# SP.net
KiCad netlist of a schematic drawn in EAGLE
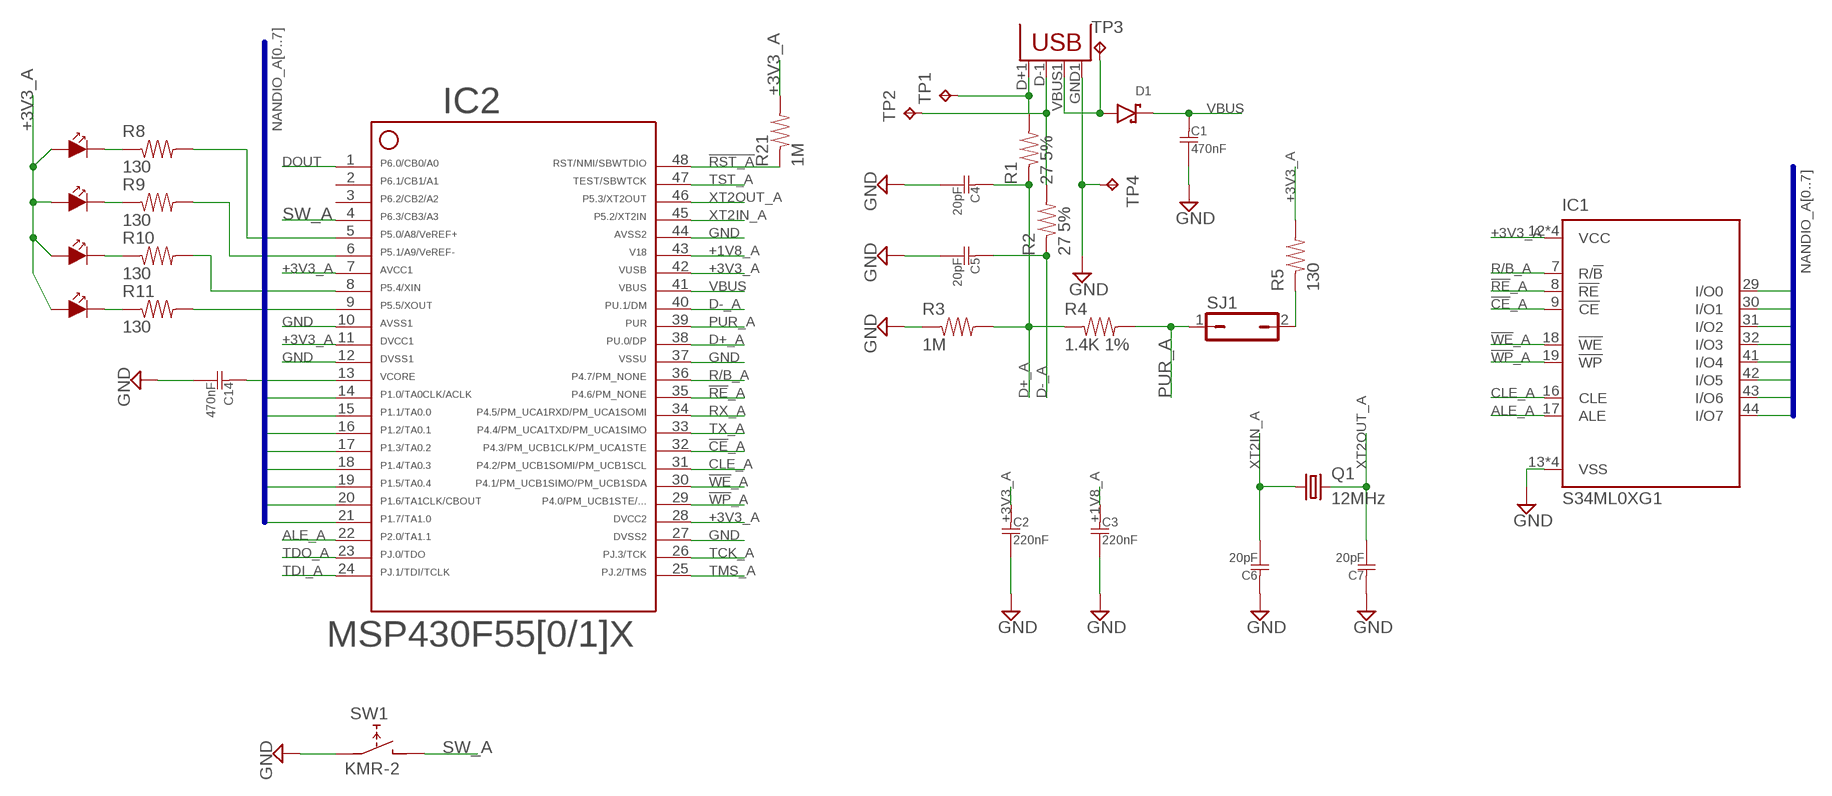
[diagram p0: schematic, sheet 1]
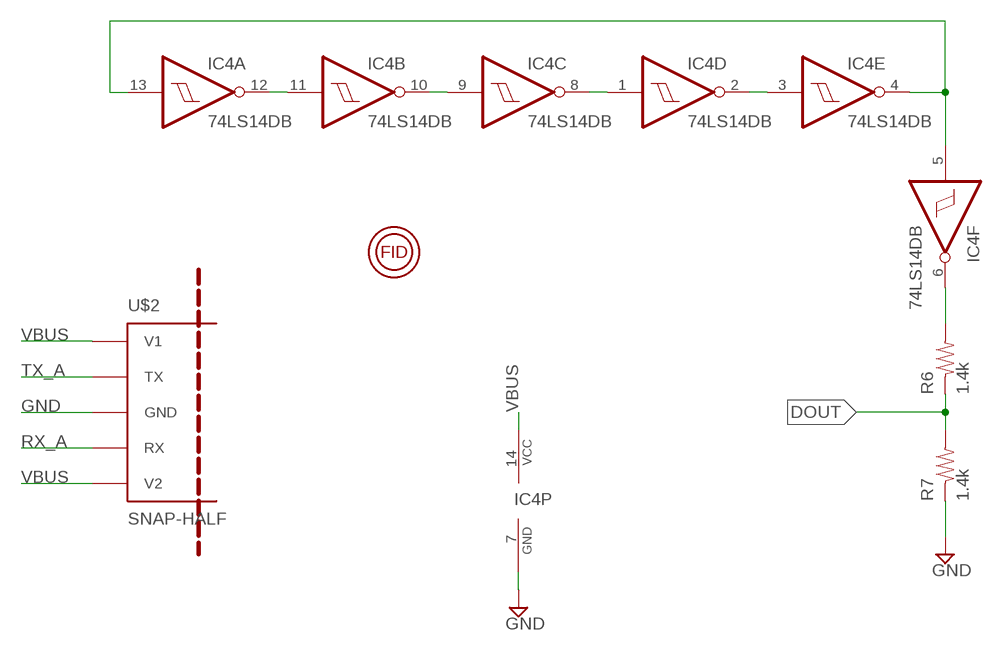
[diagram p1: schematic, sheet 2]

(export (version "E")
  (design (tool "Eeschema 10.0.6"))
  (components
    (comp (ref "IC4")
      (value "74LS14DB")
      (footprint "eagle-import:SSOP14")
      (libsource (lib "eagle-import") (part "7414DBLS"))
    )
    (comp (ref "R6")
      (value "1.4k")
      (footprint "eagle-import:R0805")
      (libsource (lib "eagle-import") (part "R0805"))
    )
    (comp (ref "R7")
      (value "1.4k")
      (footprint "eagle-import:R0805")
      (libsource (lib "eagle-import") (part "R0805"))
    )
    (comp (ref "U$2")
      (value "SNAP-HALF")
      (footprint "eagle-import:SNAP-HALF")
      (libsource (lib "eagle-import") (part "SNAP-HALF"))
    )
    (comp (ref "U$3")
      (value "FIDUCAL")
      (footprint "eagle-import:FIDUCAL")
      (libsource (lib "eagle-import") (part "FIDUCAL"))
    )
    (comp (ref "C1")
      (value "470nF")
      (footprint "eagle-import:R0805")
      (libsource (lib "eagle-import") (part "C0805"))
    )
    (comp (ref "C2")
      (value "220nF")
      (footprint "eagle-import:R0805")
      (libsource (lib "eagle-import") (part "C0805"))
    )
    (comp (ref "C3")
      (value "220nF")
      (footprint "eagle-import:R0805")
      (libsource (lib "eagle-import") (part "C0805"))
    )
    (comp (ref "C4")
      (value "20pF")
      (footprint "eagle-import:R0805")
      (libsource (lib "eagle-import") (part "C0805"))
    )
    (comp (ref "C5")
      (value "20pF")
      (footprint "eagle-import:R0805")
      (libsource (lib "eagle-import") (part "C0805"))
    )
    (comp (ref "C6")
      (value "20pF")
      (footprint "eagle-import:R0805")
      (libsource (lib "eagle-import") (part "C0805"))
    )
    (comp (ref "C7")
      (value "20pF")
      (footprint "eagle-import:R0805")
      (libsource (lib "eagle-import") (part "C0805"))
    )
    (comp (ref "C14")
      (value "470nF")
      (footprint "eagle-import:R0805")
      (libsource (lib "eagle-import") (part "C0805"))
    )
    (comp (ref "D1")
      (value "D-SCHOTTKY")
      (footprint "eagle-import:SOD123")
      (libsource (lib "eagle-import") (part "D-SCHOTTKY"))
    )
    (comp (ref "IC1")
      (value "S34ML0XG1")
      (footprint "eagle-import:TSOP48")
      (libsource (lib "eagle-import") (part "S34ML0XG1"))
    )
    (comp (ref "IC2")
      (value "F5508")
      (footprint "eagle-import:PT48")
      (libsource (lib "eagle-import") (part "F55[0/1]X---PT48"))
    )
    (comp (ref "JP1")
      (value "USBA-SMD-MALE")
      (footprint "eagle-import:USB-A-SMT-MALE")
      (libsource (lib "eagle-import") (part "USBA-SMD-MALE"))
    )
    (comp (ref "Q1")
      (value "12MHz")
      (footprint "eagle-import:CSM-3X")
      (libsource (lib "eagle-import") (part "CRYSTALCSM-3X"))
    )
    (comp (ref "R1")
      (value "27 5%")
      (footprint "eagle-import:R0805")
      (libsource (lib "eagle-import") (part "R0805"))
    )
    (comp (ref "R2")
      (value "27 5%")
      (footprint "eagle-import:R0805")
      (libsource (lib "eagle-import") (part "R0805"))
    )
    (comp (ref "R3")
      (value "1M")
      (footprint "eagle-import:R0805")
      (libsource (lib "eagle-import") (part "R0805"))
    )
    (comp (ref "R4")
      (value "1.4K 1%")
      (footprint "eagle-import:R0805")
      (libsource (lib "eagle-import") (part "R0805"))
    )
    (comp (ref "R5")
      (value "130")
      (footprint "eagle-import:R0805")
      (libsource (lib "eagle-import") (part "R0805"))
    )
    (comp (ref "R8")
      (value "130")
      (footprint "eagle-import:R0805")
      (libsource (lib "eagle-import") (part "R0805"))
    )
    (comp (ref "R9")
      (value "130")
      (footprint "eagle-import:R0805")
      (libsource (lib "eagle-import") (part "R0805"))
    )
    (comp (ref "R10")
      (value "130")
      (footprint "eagle-import:R0805")
      (libsource (lib "eagle-import") (part "R0805"))
    )
    (comp (ref "R11")
      (value "130")
      (footprint "eagle-import:R0805")
      (libsource (lib "eagle-import") (part "R0805"))
    )
    (comp (ref "R21")
      (value "1M")
      (footprint "eagle-import:R0805")
      (libsource (lib "eagle-import") (part "R0805"))
    )
    (comp (ref "SJ1")
      (value "JP1Q")
      (footprint "eagle-import:JP1")
      (libsource (lib "eagle-import") (part "JP1Q"))
    )
    (comp (ref "SW1")
      (value "KMR-2")
      (footprint "eagle-import:KMR-2-SWITCH")
      (libsource (lib "eagle-import") (part "KMR-2"))
    )
    (comp (ref "TP1")
      (value "TPTP13R")
      (footprint "eagle-import:TP13R")
      (libsource (lib "eagle-import") (part "TPTP13R"))
    )
    (comp (ref "TP2")
      (value "TPTP13R")
      (footprint "eagle-import:TP13R")
      (libsource (lib "eagle-import") (part "TPTP13R"))
    )
    (comp (ref "TP3")
      (value "TPTP13R")
      (footprint "eagle-import:TP13R")
      (libsource (lib "eagle-import") (part "TPTP13R"))
    )
    (comp (ref "TP4")
      (value "TPTP13R")
      (footprint "eagle-import:TP13R")
      (libsource (lib "eagle-import") (part "TPTP13R"))
    )
    (comp (ref "U$5")
      (value "LED")
      (footprint "eagle-import:LED0805")
      (libsource (lib "eagle-import") (part "LED"))
    )
    (comp (ref "U$6")
      (value "LED")
      (footprint "eagle-import:LED0805")
      (libsource (lib "eagle-import") (part "LED"))
    )
    (comp (ref "U$7")
      (value "LED")
      (footprint "eagle-import:LED0805")
      (libsource (lib "eagle-import") (part "LED"))
    )
    (comp (ref "U$8")
      (value "LED")
      (footprint "eagle-import:LED0805")
      (libsource (lib "eagle-import") (part "LED"))
    )
  )
  (nets
    (net (code "1") (name "+1V8_A") (class "Default")
      (node (ref "C3") (pin "P$1") (pinfunction "1_P$1") (pintype "passive"))
      (node (ref "IC2") (pin "43") (pinfunction "43_43") (pintype "power_in"))
    )
    (net (code "2") (name "+3V3_A") (class "Default")
      (node (ref "C2") (pin "P$1") (pinfunction "1_P$1") (pintype "passive"))
      (node (ref "IC1") (pin "12") (pinfunction "VCC_12") (pintype "power_in"))
      (node (ref "IC1") (pin "34") (pinfunction "VCC_34") (pintype "power_in"))
      (node (ref "IC1") (pin "37") (pinfunction "VCC_37") (pintype "power_in"))
      (node (ref "IC1") (pin "39") (pinfunction "VCC_39") (pintype "power_in"))
      (node (ref "IC2") (pin "11") (pinfunction "11_11") (pintype "power_in"))
      (node (ref "IC2") (pin "28") (pinfunction "28_28") (pintype "power_in"))
      (node (ref "IC2") (pin "42") (pinfunction "42_42") (pintype "power_in"))
      (node (ref "IC2") (pin "7") (pinfunction "7_7") (pintype "power_in"))
      (node (ref "R21") (pin "P$2") (pinfunction "2_P$2") (pintype "passive"))
      (node (ref "R5") (pin "P$2") (pinfunction "2_P$2") (pintype "passive"))
      (node (ref "U$5") (pin "ANODE") (pinfunction "ANODE_ANODE") (pintype "passive"))
      (node (ref "U$6") (pin "ANODE") (pinfunction "ANODE_ANODE") (pintype "passive"))
      (node (ref "U$7") (pin "ANODE") (pinfunction "ANODE_ANODE") (pintype "passive"))
      (node (ref "U$8") (pin "ANODE") (pinfunction "ANODE_ANODE") (pintype "passive"))
    )
    (net (code "4") (name "ALE_A") (class "Default")
      (node (ref "IC1") (pin "17") (pinfunction "ALE_17") (pintype "input"))
      (node (ref "IC2") (pin "22") (pinfunction "22_22") (pintype "bidirectional"))
    )
    (net (code "5") (name "CLE_A") (class "Default")
      (node (ref "IC1") (pin "16") (pinfunction "CLE_16") (pintype "input"))
      (node (ref "IC2") (pin "31") (pinfunction "31_31") (pintype "bidirectional"))
    )
    (net (code "6") (name "D+_A") (class "Default")
      (node (ref "C4") (pin "P$1") (pinfunction "1_P$1") (pintype "passive"))
      (node (ref "IC2") (pin "38") (pinfunction "38_38") (pintype "bidirectional"))
      (node (ref "R1") (pin "P$1") (pinfunction "1_P$1") (pintype "passive"))
      (node (ref "R3") (pin "P$2") (pinfunction "2_P$2") (pintype "passive"))
      (node (ref "R4") (pin "P$1") (pinfunction "1_P$1") (pintype "passive"))
    )
    (net (code "7") (name "D-_A") (class "Default")
      (node (ref "C5") (pin "P$1") (pinfunction "1_P$1") (pintype "passive"))
      (node (ref "IC2") (pin "40") (pinfunction "40_40") (pintype "bidirectional"))
      (node (ref "R2") (pin "P$1") (pinfunction "1_P$1") (pintype "passive"))
    )
    (net (code "8") (name "DOUT") (class "Default")
      (node (ref "IC2") (pin "1") (pinfunction "1_1") (pintype "bidirectional"))
      (node (ref "R6") (pin "P$1") (pinfunction "1_P$1") (pintype "passive"))
      (node (ref "R7") (pin "P$2") (pinfunction "2_P$2") (pintype "passive"))
    )
    (net (code "9") (name "GND") (class "Default")
      (node (ref "C1") (pin "P$2") (pinfunction "2_P$2") (pintype "passive"))
      (node (ref "C14") (pin "P$2") (pinfunction "2_P$2") (pintype "passive"))
      (node (ref "C2") (pin "P$2") (pinfunction "2_P$2") (pintype "passive"))
      (node (ref "C3") (pin "P$2") (pinfunction "2_P$2") (pintype "passive"))
      (node (ref "C4") (pin "P$2") (pinfunction "2_P$2") (pintype "passive"))
      (node (ref "C5") (pin "P$2") (pinfunction "2_P$2") (pintype "passive"))
      (node (ref "C6") (pin "P$1") (pinfunction "1_P$1") (pintype "passive"))
      (node (ref "C7") (pin "P$1") (pinfunction "1_P$1") (pintype "passive"))
      (node (ref "IC1") (pin "13") (pinfunction "VSS_13") (pintype "power_in"))
      (node (ref "IC1") (pin "25") (pinfunction "VSS_25") (pintype "power_in"))
      (node (ref "IC1") (pin "36") (pinfunction "VSS_36") (pintype "power_in"))
      (node (ref "IC1") (pin "48") (pinfunction "VSS_48") (pintype "power_in"))
      (node (ref "IC2") (pin "10") (pinfunction "10_10") (pintype "power_in"))
      (node (ref "IC2") (pin "12") (pinfunction "12_12") (pintype "power_in"))
      (node (ref "IC2") (pin "27") (pinfunction "27_27") (pintype "power_in"))
      (node (ref "IC2") (pin "37") (pinfunction "37_37") (pintype "power_in"))
      (node (ref "IC2") (pin "44") (pinfunction "44_44") (pintype "power_in"))
      (node (ref "IC4") (pin "7") (pinfunction "GND_7") (pintype "power_in"))
      (node (ref "JP1") (pin "GND1") (pinfunction "GND_GND1") (pintype "bidirectional"))
      (node (ref "R3") (pin "P$1") (pinfunction "1_P$1") (pintype "passive"))
      (node (ref "R7") (pin "P$1") (pinfunction "1_P$1") (pintype "passive"))
      (node (ref "SW1") (pin "PA1") (pinfunction "A1_PA1") (pintype "passive"))
      (node (ref "SW1") (pin "PA2") (pinfunction "A1_PA2") (pintype "passive"))
      (node (ref "TP4") (pin "TP") (pinfunction "TP_TP") (pintype "input"))
      (node (ref "U$2") (pin "P$3") (pinfunction "GND_P$3") (pintype "bidirectional"))
    )
    (net (code "10") (name "NANDIO_A0") (class "Default")
      (node (ref "IC1") (pin "29") (pinfunction "I/O0_29") (pintype "bidirectional"))
      (node (ref "IC2") (pin "14") (pinfunction "14_14") (pintype "bidirectional"))
    )
    (net (code "11") (name "NANDIO_A1") (class "Default")
      (node (ref "IC1") (pin "30") (pinfunction "I/O1_30") (pintype "bidirectional"))
      (node (ref "IC2") (pin "15") (pinfunction "15_15") (pintype "bidirectional"))
    )
    (net (code "12") (name "NANDIO_A2") (class "Default")
      (node (ref "IC1") (pin "31") (pinfunction "I/O2_31") (pintype "bidirectional"))
      (node (ref "IC2") (pin "16") (pinfunction "16_16") (pintype "bidirectional"))
    )
    (net (code "13") (name "NANDIO_A3") (class "Default")
      (node (ref "IC1") (pin "32") (pinfunction "I/O3_32") (pintype "bidirectional"))
      (node (ref "IC2") (pin "17") (pinfunction "17_17") (pintype "bidirectional"))
    )
    (net (code "14") (name "NANDIO_A4") (class "Default")
      (node (ref "IC1") (pin "41") (pinfunction "I/O4_41") (pintype "bidirectional"))
      (node (ref "IC2") (pin "18") (pinfunction "18_18") (pintype "bidirectional"))
    )
    (net (code "15") (name "NANDIO_A5") (class "Default")
      (node (ref "IC1") (pin "42") (pinfunction "I/O5_42") (pintype "bidirectional"))
      (node (ref "IC2") (pin "19") (pinfunction "19_19") (pintype "bidirectional"))
    )
    (net (code "16") (name "NANDIO_A6") (class "Default")
      (node (ref "IC1") (pin "43") (pinfunction "I/O6_43") (pintype "bidirectional"))
      (node (ref "IC2") (pin "20") (pinfunction "20_20") (pintype "bidirectional"))
    )
    (net (code "17") (name "NANDIO_A7") (class "Default")
      (node (ref "IC1") (pin "44") (pinfunction "I/O7_44") (pintype "bidirectional"))
      (node (ref "IC2") (pin "21") (pinfunction "21_21") (pintype "bidirectional"))
    )
    (net (code "18") (name "Net-(C14-1)") (class "Default")
      (node (ref "C14") (pin "P$1") (pinfunction "1_P$1") (pintype "passive"))
      (node (ref "IC2") (pin "13") (pinfunction "13_13") (pintype "power_in"))
    )
    (net (code "19") (name "Net-(IC4A-I)") (class "Default")
      (node (ref "IC4") (pin "13") (pinfunction "I_13") (pintype "input"))
      (node (ref "IC4") (pin "4") (pinfunction "O_4") (pintype "output"))
      (node (ref "IC4") (pin "5") (pinfunction "I_5") (pintype "input"))
    )
    (net (code "20") (name "Net-(IC4A-O)") (class "Default")
      (node (ref "IC4") (pin "11") (pinfunction "I_11") (pintype "input"))
      (node (ref "IC4") (pin "12") (pinfunction "O_12") (pintype "output"))
    )
    (net (code "21") (name "Net-(IC4B-O)") (class "Default")
      (node (ref "IC4") (pin "10") (pinfunction "O_10") (pintype "output"))
      (node (ref "IC4") (pin "9") (pinfunction "I_9") (pintype "input"))
    )
    (net (code "22") (name "Net-(IC4C-O)") (class "Default")
      (node (ref "IC4") (pin "1") (pinfunction "I_1") (pintype "input"))
      (node (ref "IC4") (pin "8") (pinfunction "O_8") (pintype "output"))
    )
    (net (code "23") (name "Net-(IC4D-O)") (class "Default")
      (node (ref "IC4") (pin "2") (pinfunction "O_2") (pintype "output"))
      (node (ref "IC4") (pin "3") (pinfunction "I_3") (pintype "input"))
    )
    (net (code "24") (name "Net-(IC4F-O)") (class "Default")
      (node (ref "IC4") (pin "6") (pinfunction "O_6") (pintype "output"))
      (node (ref "R6") (pin "P$2") (pinfunction "2_P$2") (pintype "passive"))
    )
    (net (code "25") (name "Net-(JP1-D+)") (class "Default")
      (node (ref "JP1") (pin "D+1") (pinfunction "D+_D+1") (pintype "bidirectional"))
      (node (ref "R1") (pin "P$2") (pinfunction "2_P$2") (pintype "passive"))
      (node (ref "TP1") (pin "TP") (pinfunction "TP_TP") (pintype "input"))
    )
    (net (code "26") (name "Net-(JP1-D-)") (class "Default")
      (node (ref "JP1") (pin "D-1") (pinfunction "D-_D-1") (pintype "bidirectional"))
      (node (ref "R2") (pin "P$2") (pinfunction "2_P$2") (pintype "passive"))
      (node (ref "TP2") (pin "TP") (pinfunction "TP_TP") (pintype "input"))
    )
    (net (code "27") (name "Net-(JP1-VBUS)") (class "Default")
      (node (ref "D1") (pin "ANODE") (pinfunction "ANODE_ANODE") (pintype "passive"))
      (node (ref "JP1") (pin "VBUS1") (pinfunction "VBUS_VBUS1") (pintype "bidirectional"))
      (node (ref "TP3") (pin "TP") (pinfunction "TP_TP") (pintype "input"))
    )
    (net (code "28") (name "Net-(R5-1)") (class "Default")
      (node (ref "R5") (pin "P$1") (pinfunction "1_P$1") (pintype "passive"))
      (node (ref "SJ1") (pin "2") (pinfunction "2_2") (pintype "passive"))
    )
    (net (code "29") (name "Net-(R8-1)") (class "Default")
      (node (ref "R8") (pin "P$1") (pinfunction "1_P$1") (pintype "passive"))
      (node (ref "U$5") (pin "CATHODE") (pinfunction "CATHODE_CATHODE") (pintype "passive"))
    )
    (net (code "30") (name "Net-(R8-2)") (class "Default")
      (node (ref "IC2") (pin "5") (pinfunction "5_5") (pintype "bidirectional"))
      (node (ref "R8") (pin "P$2") (pinfunction "2_P$2") (pintype "passive"))
    )
    (net (code "31") (name "Net-(R9-1)") (class "Default")
      (node (ref "R9") (pin "P$1") (pinfunction "1_P$1") (pintype "passive"))
      (node (ref "U$6") (pin "CATHODE") (pinfunction "CATHODE_CATHODE") (pintype "passive"))
    )
    (net (code "32") (name "Net-(R9-2)") (class "Default")
      (node (ref "IC2") (pin "6") (pinfunction "6_6") (pintype "bidirectional"))
      (node (ref "R9") (pin "P$2") (pinfunction "2_P$2") (pintype "passive"))
    )
    (net (code "33") (name "Net-(R10-1)") (class "Default")
      (node (ref "R10") (pin "P$1") (pinfunction "1_P$1") (pintype "passive"))
      (node (ref "U$7") (pin "CATHODE") (pinfunction "CATHODE_CATHODE") (pintype "passive"))
    )
    (net (code "34") (name "Net-(R10-2)") (class "Default")
      (node (ref "IC2") (pin "8") (pinfunction "8_8") (pintype "bidirectional"))
      (node (ref "R10") (pin "P$2") (pinfunction "2_P$2") (pintype "passive"))
    )
    (net (code "35") (name "Net-(R11-1)") (class "Default")
      (node (ref "R11") (pin "P$1") (pinfunction "1_P$1") (pintype "passive"))
      (node (ref "U$8") (pin "CATHODE") (pinfunction "CATHODE_CATHODE") (pintype "passive"))
    )
    (net (code "36") (name "Net-(R11-2)") (class "Default")
      (node (ref "IC2") (pin "9") (pinfunction "9_9") (pintype "bidirectional"))
      (node (ref "R11") (pin "P$2") (pinfunction "2_P$2") (pintype "passive"))
    )
    (net (code "37") (name "PUR_A") (class "Default")
      (node (ref "IC2") (pin "39") (pinfunction "39_39") (pintype "bidirectional"))
      (node (ref "R4") (pin "P$2") (pinfunction "2_P$2") (pintype "passive"))
      (node (ref "SJ1") (pin "1") (pinfunction "1_1") (pintype "passive"))
    )
    (net (code "38") (name "RX_A") (class "Default")
      (node (ref "IC2") (pin "34") (pinfunction "34_34") (pintype "bidirectional"))
      (node (ref "U$2") (pin "P$4") (pinfunction "RX_P$4") (pintype "bidirectional"))
    )
    (net (code "39") (name "R{slash}B_A") (class "Default")
      (node (ref "IC1") (pin "7") (pinfunction "R/~{B}_7") (pintype "input"))
      (node (ref "IC2") (pin "36") (pinfunction "36_36") (pintype "bidirectional"))
    )
    (net (code "40") (name "SW_A") (class "Default")
      (node (ref "IC2") (pin "4") (pinfunction "4_4") (pintype "bidirectional"))
      (node (ref "SW1") (pin "PB1") (pinfunction "B_PB1") (pintype "passive"))
      (node (ref "SW1") (pin "PB2") (pinfunction "B_PB2") (pintype "passive"))
    )
    (net (code "41") (name "TCK_A") (class "Default")
      (node (ref "IC2") (pin "26") (pinfunction "26_26") (pintype "bidirectional"))
    )
    (net (code "42") (name "TDI_A") (class "Default")
      (node (ref "IC2") (pin "24") (pinfunction "24_24") (pintype "bidirectional"))
    )
    (net (code "43") (name "TDO_A") (class "Default")
      (node (ref "IC2") (pin "23") (pinfunction "23_23") (pintype "bidirectional"))
    )
    (net (code "44") (name "TMS_A") (class "Default")
      (node (ref "IC2") (pin "25") (pinfunction "25_25") (pintype "bidirectional"))
    )
    (net (code "45") (name "TST_A") (class "Default")
      (node (ref "IC2") (pin "47") (pinfunction "47_47") (pintype "input"))
    )
    (net (code "46") (name "TX_A") (class "Default")
      (node (ref "IC2") (pin "33") (pinfunction "33_33") (pintype "bidirectional"))
      (node (ref "U$2") (pin "P$2") (pinfunction "TX_P$2") (pintype "bidirectional"))
    )
    (net (code "47") (name "VBUS") (class "Default")
      (node (ref "C1") (pin "P$1") (pinfunction "1_P$1") (pintype "passive"))
      (node (ref "D1") (pin "CATHODE") (pinfunction "CATHODE_CATHODE") (pintype "passive"))
      (node (ref "IC2") (pin "41") (pinfunction "41_41") (pintype "power_in"))
      (node (ref "IC4") (pin "14") (pinfunction "VCC_14") (pintype "power_in"))
      (node (ref "U$2") (pin "P$1") (pinfunction "V1_P$1") (pintype "bidirectional"))
      (node (ref "U$2") (pin "P$5") (pinfunction "V2_P$5") (pintype "bidirectional"))
    )
    (net (code "48") (name "XT2IN_A") (class "Default")
      (node (ref "C6") (pin "P$2") (pinfunction "2_P$2") (pintype "passive"))
      (node (ref "IC2") (pin "45") (pinfunction "45_45") (pintype "bidirectional"))
      (node (ref "Q1") (pin "P$1") (pinfunction "1_P$1") (pintype "passive"))
    )
    (net (code "49") (name "XT2OUT_A") (class "Default")
      (node (ref "C7") (pin "P$2") (pinfunction "2_P$2") (pintype "passive"))
      (node (ref "IC2") (pin "46") (pinfunction "46_46") (pintype "power_in"))
      (node (ref "Q1") (pin "P$2") (pinfunction "2_P$2") (pintype "passive"))
    )
    (net (code "50") (name "unconnected-(IC2-Pad2)") (class "Default")
      (node (ref "IC2") (pin "2") (pinfunction "2_2") (pintype "bidirectional"))
    )
    (net (code "51") (name "unconnected-(IC2-Pad3)") (class "Default")
      (node (ref "IC2") (pin "3") (pinfunction "3_3") (pintype "bidirectional"))
    )
    (net (code "52") (name "~{CE}_A") (class "Default")
      (node (ref "IC1") (pin "9") (pinfunction "~{CE}_9") (pintype "input"))
      (node (ref "IC2") (pin "32") (pinfunction "32_32") (pintype "bidirectional"))
    )
    (net (code "53") (name "~{RE}_A") (class "Default")
      (node (ref "IC1") (pin "8") (pinfunction "~{RE}_8") (pintype "input"))
      (node (ref "IC2") (pin "35") (pinfunction "35_35") (pintype "bidirectional"))
    )
    (net (code "54") (name "~{RST_A}") (class "Default")
      (node (ref "IC2") (pin "48") (pinfunction "48_48") (pintype "bidirectional"))
      (node (ref "R21") (pin "P$1") (pinfunction "1_P$1") (pintype "passive"))
    )
    (net (code "55") (name "~{WE}_A") (class "Default")
      (node (ref "IC1") (pin "18") (pinfunction "~{WE}_18") (pintype "input"))
      (node (ref "IC2") (pin "30") (pinfunction "30_30") (pintype "bidirectional"))
    )
    (net (code "56") (name "~{WP}_A") (class "Default")
      (node (ref "IC1") (pin "19") (pinfunction "~{WP}_19") (pintype "input"))
      (node (ref "IC2") (pin "29") (pinfunction "29_29") (pintype "bidirectional"))
    )
  )
)
